# USB.net
KiCad netlist of a schematic drawn in Altium Designer
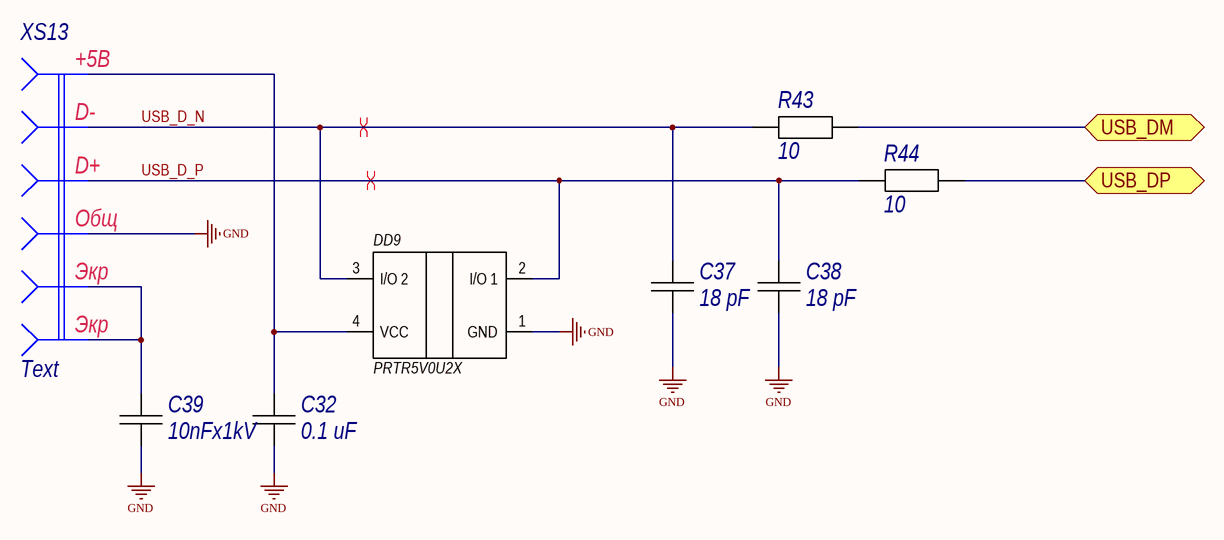
[diagram p0: USB.SchDoc]

(export (version "E")
  (design (tool "Eeschema 10.0.6"))
  (components
    (comp (ref "C32")
      (value "0.1 uF")
      (footprint "C0805C")
      (fields (field (name "PUBLISHER") "Andrew Danich"))
      (libsource (lib "PA_control_board") (part "CAP_0805"))
    )
    (comp (ref "C37")
      (value "18 pF")
      (footprint "C0805C")
      (fields (field (name "PUBLISHER") "Andrew Danich"))
      (libsource (lib "PA_control_board") (part "CAP_0805"))
    )
    (comp (ref "C38")
      (value "18 pF")
      (footprint "C0805C")
      (fields (field (name "PUBLISHER") "Andrew Danich"))
      (libsource (lib "PA_control_board") (part "CAP_0805"))
    )
    (comp (ref "C39")
      (value "10nFx1kV")
      (footprint "C0805C")
      (fields (field (name "PUBLISHER") "Andrew Danich"))
      (libsource (lib "PA_control_board") (part "CAP_1206"))
    )
    (comp (ref "DD9")
      (value "PRTR5V0U2X")
      (footprint "SOT143B")
      (description "Ultra low capacitance double rail-to-rail ESD protection diode")
      (fields (field (name "MP") "PRTR5V0U2X,215"))
      (libsource (lib "PA_control_board") (part "PRTR5V0U2X,215"))
    )
    (comp (ref "R43")
      (value "10")
      (footprint "C0805R")
      (fields (field (name "PUBLISHER") "Andrew Danich"))
      (libsource (lib "PA_control_board") (part "RES_0805"))
    )
    (comp (ref "R44")
      (value "10")
      (footprint "C0805R")
      (fields (field (name "PUBLISHER") "Andrew Danich"))
      (libsource (lib "PA_control_board") (part "RES_0805"))
    )
    (comp (ref "XS13")
      (value "Text")
      (footprint "SAMTEC_USB-B-S-X-X-TH")
      (fields (field (name "PUBLISHER") "Andrew Danich"))
      (libsource (lib "PA_control_board") (part "CONNECT_USB"))
    )
  )
  (nets
    (net (code "1") (name "/USB_DM") (class "Default")
      (node (ref "R43") (pin "1") (pinfunction "1_1") (pintype "passive"))
    )
    (net (code "2") (name "/USB_DP") (class "Default")
      (node (ref "R44") (pin "1") (pinfunction "1_1") (pintype "passive"))
    )
    (net (code "3") (name "/USB_D_N") (class "Default")
      (node (ref "C37") (pin "2") (pinfunction "2_2") (pintype "passive"))
      (node (ref "DD9") (pin "3") (pinfunction "I/O_2_3") (pintype "passive"))
      (node (ref "R43") (pin "2") (pinfunction "2_2") (pintype "passive"))
      (node (ref "XS13") (pin "2") (pintype "passive"))
    )
    (net (code "4") (name "/USB_D_P") (class "Default")
      (node (ref "C38") (pin "2") (pinfunction "2_2") (pintype "passive"))
      (node (ref "DD9") (pin "2") (pinfunction "I/O_1_2") (pintype "passive"))
      (node (ref "R44") (pin "2") (pinfunction "2_2") (pintype "passive"))
      (node (ref "XS13") (pin "3") (pintype "passive"))
    )
    (net (code "5") (name "GND") (class "Default")
      (node (ref "C32") (pin "1") (pinfunction "1_1") (pintype "passive"))
      (node (ref "C37") (pin "1") (pinfunction "1_1") (pintype "passive"))
      (node (ref "C38") (pin "1") (pinfunction "1_1") (pintype "passive"))
      (node (ref "C39") (pin "1") (pinfunction "1_1") (pintype "passive"))
      (node (ref "DD9") (pin "1") (pinfunction "GND_1") (pintype "passive"))
      (node (ref "XS13") (pin "4") (pintype "passive"))
    )
    (net (code "6") (name "Net-(C39-Pad2)") (class "Default")
      (node (ref "C39") (pin "2") (pinfunction "2_2") (pintype "passive"))
      (node (ref "XS13") (pin "S1") (pintype "passive"))
      (node (ref "XS13") (pin "S2") (pintype "passive"))
    )
    (net (code "7") (name "Net-(DD9-VCC)") (class "Default")
      (node (ref "C32") (pin "2") (pinfunction "2_2") (pintype "passive"))
      (node (ref "DD9") (pin "4") (pinfunction "VCC_4") (pintype "passive"))
      (node (ref "XS13") (pin "1") (pintype "passive"))
    )
  )
)
